# ugs_wifi_pendant_easyeda_source.net
KiCad netlist of a schematic drawn in EasyEDA
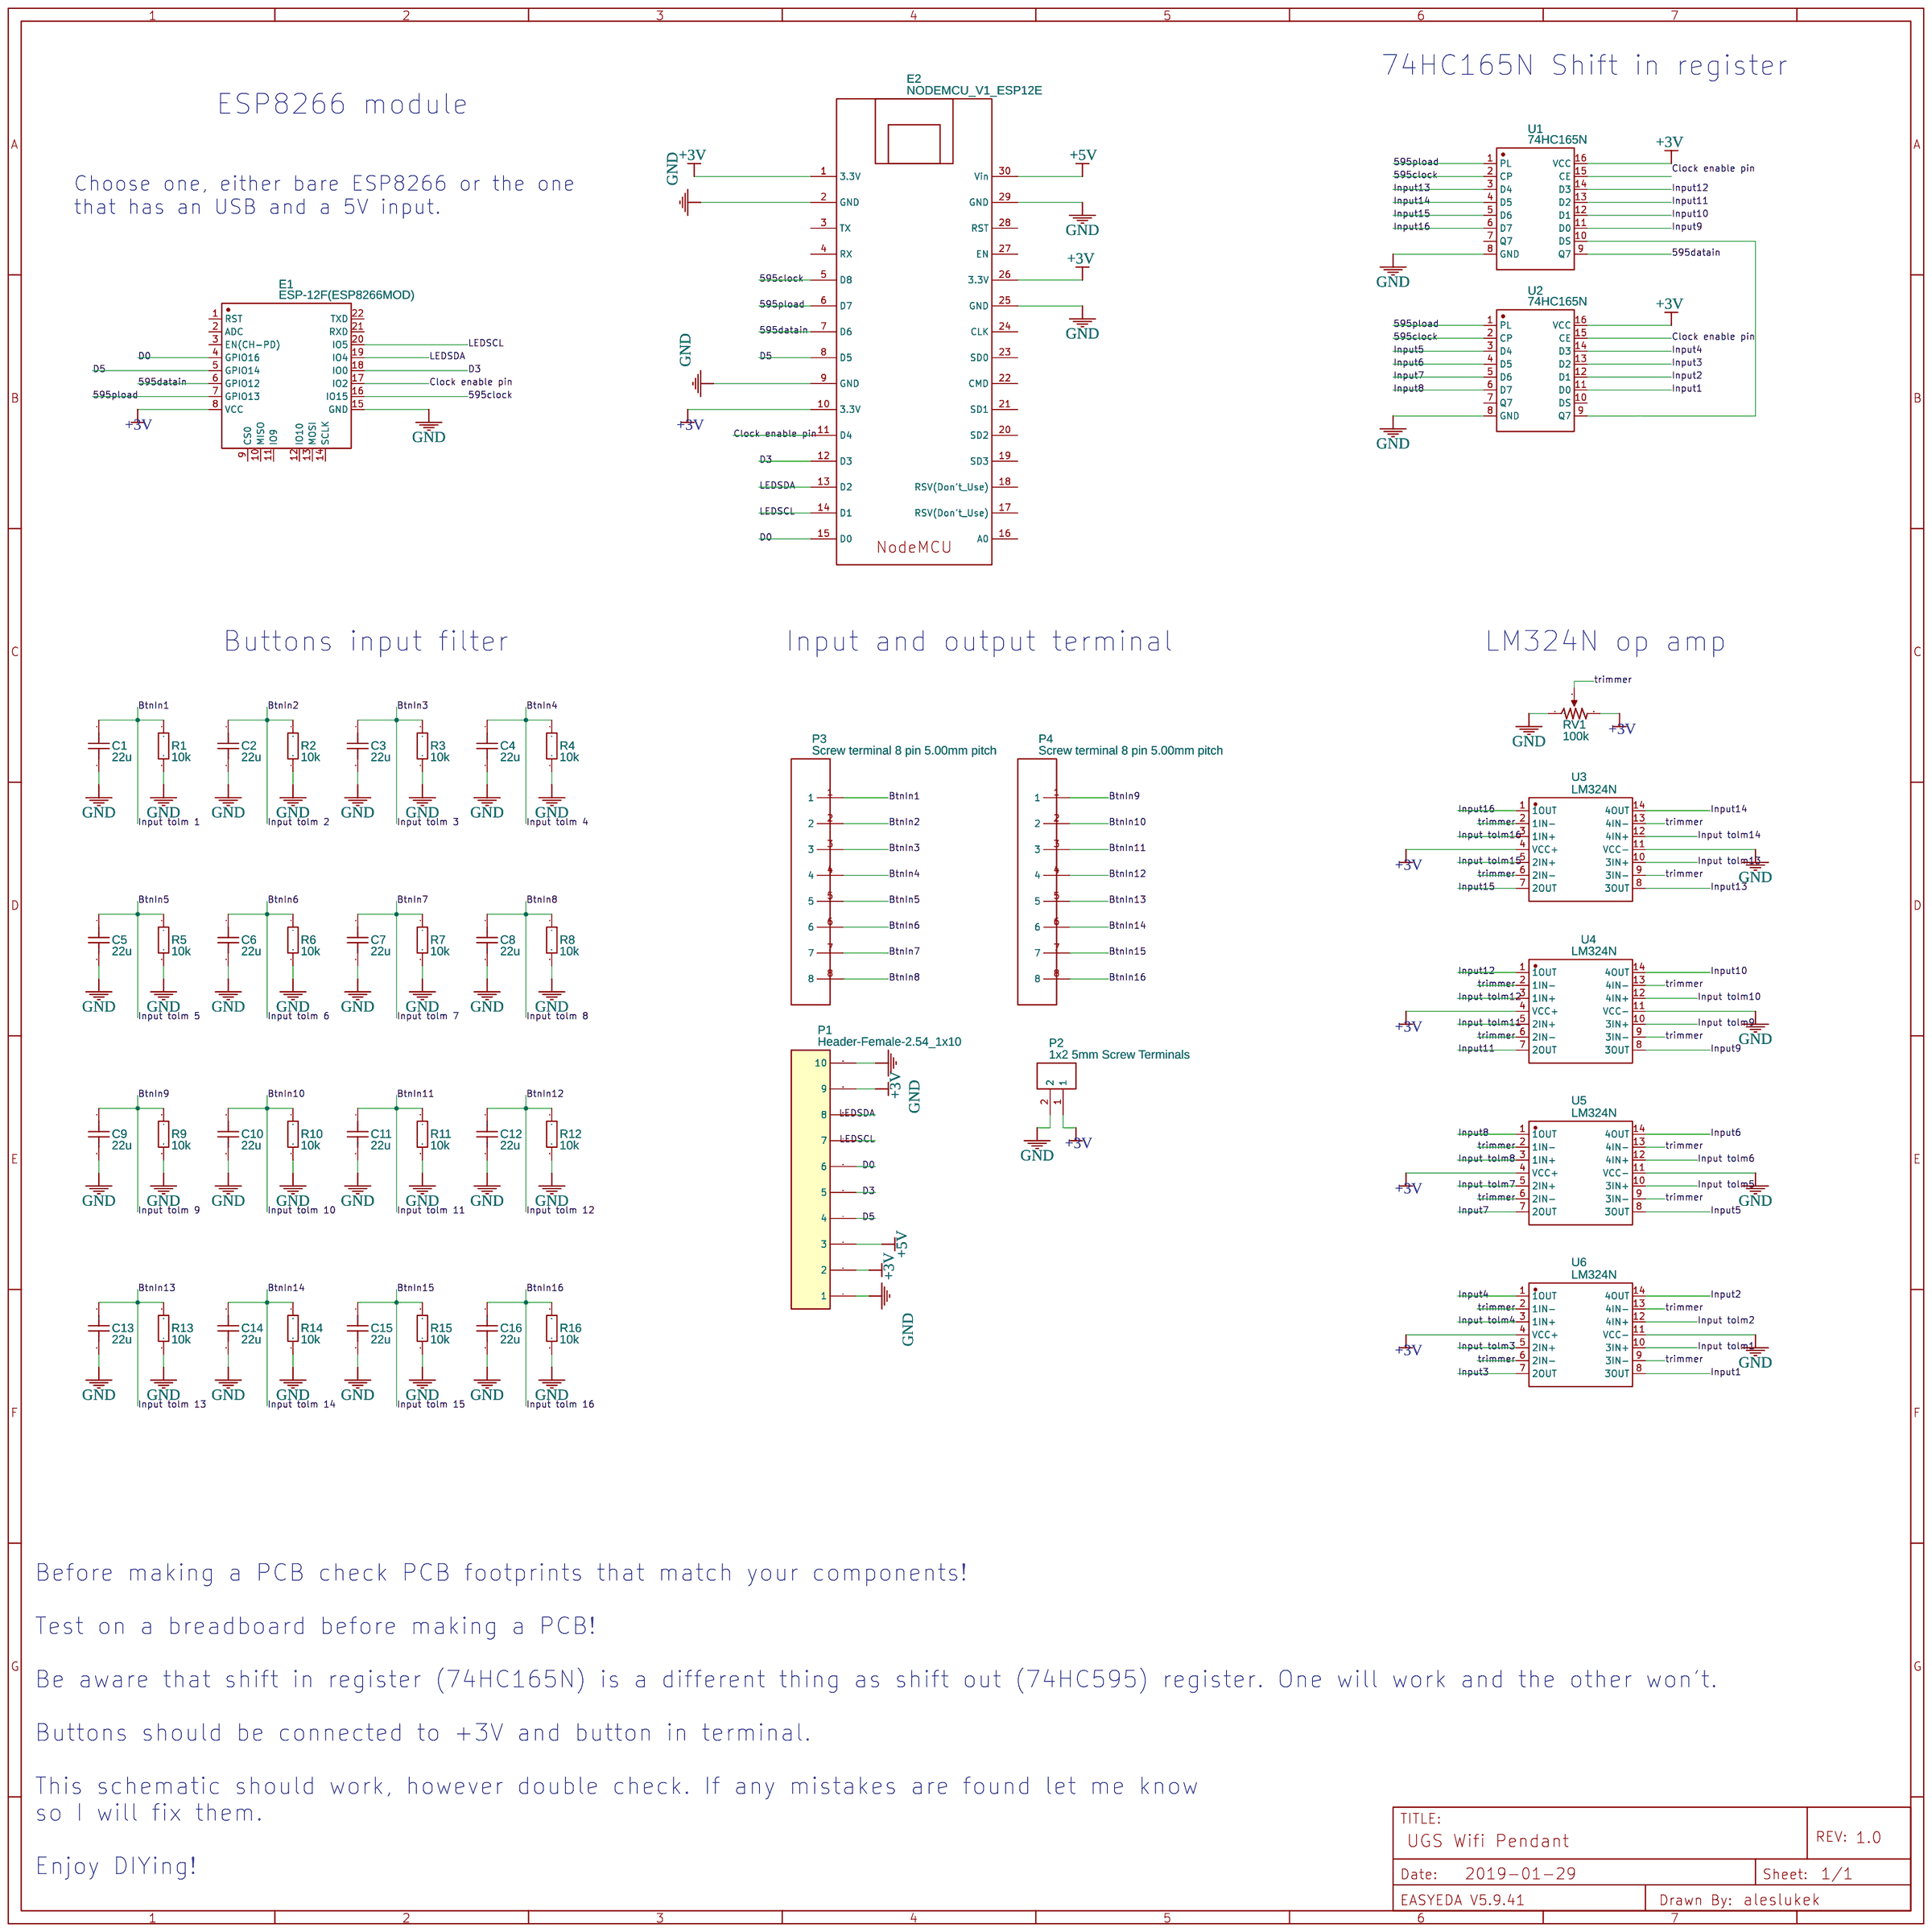
[diagram p0: schematic sheet]

(export (version "E")
  (design (tool "Eeschema 10.0.6"))
  (components
    (comp (ref "C1")
      (value "22u")
      (fields (field (name "BOM_Manufacturer Part") "?"))
      (libsource (lib "") (part "Cap_RAD-0.1_US"))
    )
    (comp (ref "C2")
      (value "22u")
      (fields (field (name "BOM_Manufacturer Part") "?"))
      (libsource (lib "") (part "Cap_RAD-0.1_US"))
    )
    (comp (ref "C3")
      (value "22u")
      (fields (field (name "BOM_Manufacturer Part") "?"))
      (libsource (lib "") (part "Cap_RAD-0.1_US"))
    )
    (comp (ref "C4")
      (value "22u")
      (fields (field (name "BOM_Manufacturer Part") "?"))
      (libsource (lib "") (part "Cap_RAD-0.1_US"))
    )
    (comp (ref "C5")
      (value "22u")
      (fields (field (name "BOM_Manufacturer Part") "?"))
      (libsource (lib "") (part "Cap_RAD-0.1_US"))
    )
    (comp (ref "C6")
      (value "22u")
      (fields (field (name "BOM_Manufacturer Part") "?"))
      (libsource (lib "") (part "Cap_RAD-0.1_US"))
    )
    (comp (ref "C7")
      (value "22u")
      (fields (field (name "BOM_Manufacturer Part") "?"))
      (libsource (lib "") (part "Cap_RAD-0.1_US"))
    )
    (comp (ref "C8")
      (value "22u")
      (fields (field (name "BOM_Manufacturer Part") "?"))
      (libsource (lib "") (part "Cap_RAD-0.1_US"))
    )
    (comp (ref "C9")
      (value "22u")
      (fields (field (name "BOM_Manufacturer Part") "?"))
      (libsource (lib "") (part "Cap_RAD-0.1_US"))
    )
    (comp (ref "C10")
      (value "22u")
      (fields (field (name "BOM_Manufacturer Part") "?"))
      (libsource (lib "") (part "Cap_RAD-0.1_US"))
    )
    (comp (ref "C11")
      (value "22u")
      (fields (field (name "BOM_Manufacturer Part") "?"))
      (libsource (lib "") (part "Cap_RAD-0.1_US"))
    )
    (comp (ref "C12")
      (value "22u")
      (fields (field (name "BOM_Manufacturer Part") "?"))
      (libsource (lib "") (part "Cap_RAD-0.1_US"))
    )
    (comp (ref "C13")
      (value "22u")
      (fields (field (name "BOM_Manufacturer Part") "?"))
      (libsource (lib "") (part "Cap_RAD-0.1_US"))
    )
    (comp (ref "C14")
      (value "22u")
      (fields (field (name "BOM_Manufacturer Part") "?"))
      (libsource (lib "") (part "Cap_RAD-0.1_US"))
    )
    (comp (ref "C15")
      (value "22u")
      (fields (field (name "BOM_Manufacturer Part") "?"))
      (libsource (lib "") (part "Cap_RAD-0.1_US"))
    )
    (comp (ref "C16")
      (value "22u")
      (fields (field (name "BOM_Manufacturer Part") "?"))
      (libsource (lib "") (part "Cap_RAD-0.1_US"))
    )
    (comp (ref "E1")
      (value "ESP-12F(ESP8266MOD)")
      (fields (field (name "BOM_Supplier Part") "C82891"))
      (libsource (lib "") (part "Unknown_215_290"))
    )
    (comp (ref "E2")
      (value "NODEMCU_V1_ESP12E")
      (fields (field (name "BOM_Manufacturer Part") "?"))
      (libsource (lib "") (part "NODEMCU_V1_ESP12E"))
    )
    (comp (ref "P1")
      (value "Header-Female-2.54_1x10")
      (fields (field (name "BOM_Supplier Part") "C35445"))
      (libsource (lib "") (part "Unknown_635_885"))
    )
    (comp (ref "P2") (value "1x2 5mm Screw Terminals") (libsource (lib "") (part "Unknown_805_835")))
    (comp (ref "P3")
      (value "Screw terminal 8 pin 5.00mm pitch")
      (fields (field (name "BOM_Manufacturer Part") "?"))
      (libsource (lib "") (part "Unknown_605_700"))
    )
    (comp (ref "P4")
      (value "Screw terminal 8 pin 5.00mm pitch")
      (fields (field (name "BOM_Manufacturer Part") "?"))
      (libsource (lib "") (part "Unknown_780_700"))
    )
    (comp (ref "R1")
      (value "10k")
      (fields (field (name "BOM_Manufacturer Part") "?"))
      (libsource (lib "") (part "Res_AXIAL-0.3(1/8W)_EU"))
    )
    (comp (ref "R2")
      (value "10k")
      (fields (field (name "BOM_Manufacturer Part") "?"))
      (libsource (lib "") (part "Res_AXIAL-0.3(1/8W)_EU"))
    )
    (comp (ref "R3")
      (value "10k")
      (fields (field (name "BOM_Manufacturer Part") "?"))
      (libsource (lib "") (part "Res_AXIAL-0.3(1/8W)_EU"))
    )
    (comp (ref "R4")
      (value "10k")
      (fields (field (name "BOM_Manufacturer Part") "?"))
      (libsource (lib "") (part "Res_AXIAL-0.3(1/8W)_EU"))
    )
    (comp (ref "R5")
      (value "10k")
      (fields (field (name "BOM_Manufacturer Part") "?"))
      (libsource (lib "") (part "Res_AXIAL-0.3(1/8W)_EU"))
    )
    (comp (ref "R6")
      (value "10k")
      (fields (field (name "BOM_Manufacturer Part") "?"))
      (libsource (lib "") (part "Res_AXIAL-0.3(1/8W)_EU"))
    )
    (comp (ref "R7")
      (value "10k")
      (fields (field (name "BOM_Manufacturer Part") "?"))
      (libsource (lib "") (part "Res_AXIAL-0.3(1/8W)_EU"))
    )
    (comp (ref "R8")
      (value "10k")
      (fields (field (name "BOM_Manufacturer Part") "?"))
      (libsource (lib "") (part "Res_AXIAL-0.3(1/8W)_EU"))
    )
    (comp (ref "R9")
      (value "10k")
      (fields (field (name "BOM_Manufacturer Part") "?"))
      (libsource (lib "") (part "Res_AXIAL-0.3(1/8W)_EU"))
    )
    (comp (ref "R10")
      (value "10k")
      (fields (field (name "BOM_Manufacturer Part") "?"))
      (libsource (lib "") (part "Res_AXIAL-0.3(1/8W)_EU"))
    )
    (comp (ref "R11")
      (value "10k")
      (fields (field (name "BOM_Manufacturer Part") "?"))
      (libsource (lib "") (part "Res_AXIAL-0.3(1/8W)_EU"))
    )
    (comp (ref "R12")
      (value "10k")
      (fields (field (name "BOM_Manufacturer Part") "?"))
      (libsource (lib "") (part "Res_AXIAL-0.3(1/8W)_EU"))
    )
    (comp (ref "R13")
      (value "10k")
      (fields (field (name "BOM_Manufacturer Part") "?"))
      (libsource (lib "") (part "Res_AXIAL-0.3(1/8W)_EU"))
    )
    (comp (ref "R14")
      (value "10k")
      (fields (field (name "BOM_Manufacturer Part") "?"))
      (libsource (lib "") (part "Res_AXIAL-0.3(1/8W)_EU"))
    )
    (comp (ref "R15")
      (value "10k")
      (fields (field (name "BOM_Manufacturer Part") "?"))
      (libsource (lib "") (part "Res_AXIAL-0.3(1/8W)_EU"))
    )
    (comp (ref "R16")
      (value "10k")
      (fields (field (name "BOM_Manufacturer Part") "?"))
      (libsource (lib "") (part "Res_AXIAL-0.3(1/8W)_EU"))
    )
    (comp (ref "RV1")
      (value "100k")
      (fields (field (name "BOM_Manufacturer Part") "?"))
      (libsource (lib "") (part "trimmer"))
    )
    (comp (ref "U1")
      (value "74HC165N")
      (fields (field (name "BOM_Manufacturer Part") "?"))
      (libsource (lib "") (part "Unknown_1180_110"))
    )
    (comp (ref "U2")
      (value "74HC165N")
      (fields (field (name "BOM_Manufacturer Part") "?"))
      (libsource (lib "") (part "Unknown_1180_235"))
    )
    (comp (ref "U3")
      (value "LM324N")
      (fields (field (name "BOM_Supplier Part") "C114380"))
      (libsource (lib "") (part "Unknown_1215_650"))
    )
    (comp (ref "U4")
      (value "LM324N")
      (fields (field (name "BOM_Supplier Part") "C114380"))
      (libsource (lib "") (part "Unknown_1215_775"))
    )
    (comp (ref "U5")
      (value "LM324N")
      (fields (field (name "BOM_Supplier Part") "C114380"))
      (libsource (lib "") (part "Unknown_1215_900"))
    )
    (comp (ref "U6")
      (value "LM324N")
      (fields (field (name "BOM_Supplier Part") "C114380"))
      (libsource (lib "") (part "Unknown_1215_1025"))
    )
  )
  (nets
    (net (code "1") (name "+3V") (class "Default")
      (node (ref "E1") (pin "8") (pinfunction "VCC_8") (pintype "unspecified"))
      (node (ref "E2") (pin "1") (pinfunction "3.3V_1") (pintype "unspecified"))
      (node (ref "E2") (pin "10") (pinfunction "3.3V_10") (pintype "unspecified"))
      (node (ref "E2") (pin "26") (pinfunction "3.3V_26") (pintype "unspecified"))
      (node (ref "P1") (pin "2") (pinfunction "2_2") (pintype "input"))
      (node (ref "P1") (pin "9") (pinfunction "9_9") (pintype "input"))
      (node (ref "P2") (pin "1") (pinfunction "1_1") (pintype "unspecified"))
      (node (ref "RV1") (pin "3") (pinfunction "3_3") (pintype "unspecified"))
      (node (ref "U1") (pin "16") (pinfunction "VCC_16") (pintype "unspecified"))
      (node (ref "U2") (pin "16") (pinfunction "VCC_16") (pintype "unspecified"))
      (node (ref "U3") (pin "4") (pinfunction "VCC+_4") (pintype "unspecified"))
      (node (ref "U4") (pin "4") (pinfunction "VCC+_4") (pintype "unspecified"))
      (node (ref "U5") (pin "4") (pinfunction "VCC+_4") (pintype "unspecified"))
      (node (ref "U6") (pin "4") (pinfunction "VCC+_4") (pintype "unspecified"))
    )
    (net (code "2") (name "+5V") (class "Default")
      (node (ref "E2") (pin "30") (pinfunction "Vin_30") (pintype "unspecified"))
      (node (ref "P1") (pin "3") (pinfunction "3_3") (pintype "input"))
    )
    (net (code "3") (name "/595clock") (class "Default")
      (node (ref "E1") (pin "16") (pinfunction "IO15_16") (pintype "unspecified"))
      (node (ref "E2") (pin "5") (pinfunction "D8_5") (pintype "unspecified"))
      (node (ref "U1") (pin "2") (pinfunction "CP_2") (pintype "unspecified"))
      (node (ref "U2") (pin "2") (pinfunction "CP_2") (pintype "unspecified"))
    )
    (net (code "4") (name "/595datain") (class "Default")
      (node (ref "E1") (pin "6") (pinfunction "GPIO12_6") (pintype "unspecified"))
      (node (ref "E2") (pin "7") (pinfunction "D6_7") (pintype "unspecified"))
      (node (ref "U1") (pin "9") (pinfunction "Q7_9") (pintype "unspecified"))
    )
    (net (code "5") (name "/595pload") (class "Default")
      (node (ref "E1") (pin "7") (pinfunction "GPIO13_7") (pintype "unspecified"))
      (node (ref "E2") (pin "6") (pinfunction "D7_6") (pintype "unspecified"))
      (node (ref "U1") (pin "1") (pinfunction "PL_1") (pintype "unspecified"))
      (node (ref "U2") (pin "1") (pinfunction "PL_1") (pintype "unspecified"))
    )
    (net (code "6") (name "/BtnIn1") (class "Default")
      (node (ref "C1") (pin "1") (pinfunction "1_1") (pintype "unspecified"))
      (node (ref "P3") (pin "1") (pinfunction "1_1") (pintype "unspecified"))
      (node (ref "R1") (pin "1") (pinfunction "1_1") (pintype "unspecified"))
    )
    (net (code "7") (name "/BtnIn2") (class "Default")
      (node (ref "C2") (pin "1") (pinfunction "1_1") (pintype "unspecified"))
      (node (ref "P3") (pin "2") (pinfunction "2_2") (pintype "unspecified"))
      (node (ref "R2") (pin "1") (pinfunction "1_1") (pintype "unspecified"))
    )
    (net (code "8") (name "/BtnIn3") (class "Default")
      (node (ref "C3") (pin "1") (pinfunction "1_1") (pintype "unspecified"))
      (node (ref "P3") (pin "3") (pinfunction "3_3") (pintype "unspecified"))
      (node (ref "R3") (pin "1") (pinfunction "1_1") (pintype "unspecified"))
    )
    (net (code "9") (name "/BtnIn4") (class "Default")
      (node (ref "C4") (pin "1") (pinfunction "1_1") (pintype "unspecified"))
      (node (ref "P3") (pin "4") (pinfunction "4_4") (pintype "unspecified"))
      (node (ref "R4") (pin "1") (pinfunction "1_1") (pintype "unspecified"))
    )
    (net (code "10") (name "/BtnIn5") (class "Default")
      (node (ref "C5") (pin "1") (pinfunction "1_1") (pintype "unspecified"))
      (node (ref "P3") (pin "5") (pinfunction "5_5") (pintype "unspecified"))
      (node (ref "R5") (pin "1") (pinfunction "1_1") (pintype "unspecified"))
    )
    (net (code "11") (name "/BtnIn6") (class "Default")
      (node (ref "C6") (pin "1") (pinfunction "1_1") (pintype "unspecified"))
      (node (ref "P3") (pin "6") (pinfunction "6_6") (pintype "unspecified"))
      (node (ref "R6") (pin "1") (pinfunction "1_1") (pintype "unspecified"))
    )
    (net (code "12") (name "/BtnIn7") (class "Default")
      (node (ref "C7") (pin "1") (pinfunction "1_1") (pintype "unspecified"))
      (node (ref "P3") (pin "7") (pinfunction "7_7") (pintype "unspecified"))
      (node (ref "R7") (pin "1") (pinfunction "1_1") (pintype "unspecified"))
    )
    (net (code "13") (name "/BtnIn8") (class "Default")
      (node (ref "C8") (pin "1") (pinfunction "1_1") (pintype "unspecified"))
      (node (ref "P3") (pin "8") (pinfunction "8_8") (pintype "unspecified"))
      (node (ref "R8") (pin "1") (pinfunction "1_1") (pintype "unspecified"))
    )
    (net (code "14") (name "/BtnIn9") (class "Default")
      (node (ref "C9") (pin "1") (pinfunction "1_1") (pintype "unspecified"))
      (node (ref "P4") (pin "1") (pinfunction "1_1") (pintype "unspecified"))
      (node (ref "R9") (pin "1") (pinfunction "1_1") (pintype "unspecified"))
    )
    (net (code "15") (name "/BtnIn10") (class "Default")
      (node (ref "C10") (pin "1") (pinfunction "1_1") (pintype "unspecified"))
      (node (ref "P4") (pin "2") (pinfunction "2_2") (pintype "unspecified"))
      (node (ref "R10") (pin "1") (pinfunction "1_1") (pintype "unspecified"))
    )
    (net (code "16") (name "/BtnIn11") (class "Default")
      (node (ref "C11") (pin "1") (pinfunction "1_1") (pintype "unspecified"))
      (node (ref "P4") (pin "3") (pinfunction "3_3") (pintype "unspecified"))
      (node (ref "R11") (pin "1") (pinfunction "1_1") (pintype "unspecified"))
    )
    (net (code "17") (name "/BtnIn12") (class "Default")
      (node (ref "C12") (pin "1") (pinfunction "1_1") (pintype "unspecified"))
      (node (ref "P4") (pin "4") (pinfunction "4_4") (pintype "unspecified"))
      (node (ref "R12") (pin "1") (pinfunction "1_1") (pintype "unspecified"))
    )
    (net (code "18") (name "/BtnIn13") (class "Default")
      (node (ref "C13") (pin "1") (pinfunction "1_1") (pintype "unspecified"))
      (node (ref "P4") (pin "5") (pinfunction "5_5") (pintype "unspecified"))
      (node (ref "R13") (pin "1") (pinfunction "1_1") (pintype "unspecified"))
    )
    (net (code "19") (name "/BtnIn14") (class "Default")
      (node (ref "C14") (pin "1") (pinfunction "1_1") (pintype "unspecified"))
      (node (ref "P4") (pin "6") (pinfunction "6_6") (pintype "unspecified"))
      (node (ref "R14") (pin "1") (pinfunction "1_1") (pintype "unspecified"))
    )
    (net (code "20") (name "/BtnIn15") (class "Default")
      (node (ref "C15") (pin "1") (pinfunction "1_1") (pintype "unspecified"))
      (node (ref "P4") (pin "7") (pinfunction "7_7") (pintype "unspecified"))
      (node (ref "R15") (pin "1") (pinfunction "1_1") (pintype "unspecified"))
    )
    (net (code "21") (name "/BtnIn16") (class "Default")
      (node (ref "C16") (pin "1") (pinfunction "1_1") (pintype "unspecified"))
      (node (ref "P4") (pin "8") (pinfunction "8_8") (pintype "unspecified"))
      (node (ref "R16") (pin "1") (pinfunction "1_1") (pintype "unspecified"))
    )
    (net (code "22") (name "/Clock enable pin") (class "Default")
      (node (ref "E1") (pin "17") (pinfunction "IO2_17") (pintype "unspecified"))
      (node (ref "E2") (pin "11") (pinfunction "D4_11") (pintype "unspecified"))
      (node (ref "U2") (pin "15") (pinfunction "CE_15") (pintype "unspecified"))
    )
    (net (code "23") (name "/D0") (class "Default")
      (node (ref "E1") (pin "4") (pinfunction "GPIO16_4") (pintype "unspecified"))
      (node (ref "E2") (pin "15") (pinfunction "D0_15") (pintype "unspecified"))
      (node (ref "P1") (pin "6") (pinfunction "6_6") (pintype "input"))
    )
    (net (code "24") (name "/D3") (class "Default")
      (node (ref "E1") (pin "18") (pinfunction "IO0_18") (pintype "unspecified"))
      (node (ref "E2") (pin "12") (pinfunction "D3_12") (pintype "unspecified"))
      (node (ref "P1") (pin "5") (pinfunction "5_5") (pintype "input"))
    )
    (net (code "25") (name "/D5") (class "Default")
      (node (ref "E1") (pin "5") (pinfunction "GPIO14_5") (pintype "unspecified"))
      (node (ref "E2") (pin "8") (pinfunction "D5_8") (pintype "unspecified"))
      (node (ref "P1") (pin "4") (pinfunction "4_4") (pintype "input"))
    )
    (net (code "26") (name "/Input tolm1") (class "Default")
      (node (ref "U6") (pin "10") (pinfunction "3IN+_10") (pintype "unspecified"))
    )
    (net (code "27") (name "/Input tolm2") (class "Default")
      (node (ref "U6") (pin "12") (pinfunction "4IN+_12") (pintype "unspecified"))
    )
    (net (code "28") (name "/Input tolm3") (class "Default")
      (node (ref "U6") (pin "5") (pinfunction "2IN+_5") (pintype "unspecified"))
    )
    (net (code "29") (name "/Input tolm4") (class "Default")
      (node (ref "U6") (pin "3") (pinfunction "1IN+_3") (pintype "unspecified"))
    )
    (net (code "30") (name "/Input tolm5") (class "Default")
      (node (ref "U5") (pin "10") (pinfunction "3IN+_10") (pintype "unspecified"))
    )
    (net (code "31") (name "/Input tolm6") (class "Default")
      (node (ref "U5") (pin "12") (pinfunction "4IN+_12") (pintype "unspecified"))
    )
    (net (code "32") (name "/Input tolm7") (class "Default")
      (node (ref "U5") (pin "5") (pinfunction "2IN+_5") (pintype "unspecified"))
    )
    (net (code "33") (name "/Input tolm8") (class "Default")
      (node (ref "U5") (pin "3") (pinfunction "1IN+_3") (pintype "unspecified"))
    )
    (net (code "34") (name "/Input tolm9") (class "Default")
      (node (ref "U4") (pin "10") (pinfunction "3IN+_10") (pintype "unspecified"))
    )
    (net (code "35") (name "/Input tolm10") (class "Default")
      (node (ref "U4") (pin "12") (pinfunction "4IN+_12") (pintype "unspecified"))
    )
    (net (code "36") (name "/Input tolm11") (class "Default")
      (node (ref "U4") (pin "5") (pinfunction "2IN+_5") (pintype "unspecified"))
    )
    (net (code "37") (name "/Input tolm12") (class "Default")
      (node (ref "U4") (pin "3") (pinfunction "1IN+_3") (pintype "unspecified"))
    )
    (net (code "38") (name "/Input tolm13") (class "Default")
      (node (ref "U3") (pin "10") (pinfunction "3IN+_10") (pintype "unspecified"))
    )
    (net (code "39") (name "/Input tolm14") (class "Default")
      (node (ref "U3") (pin "12") (pinfunction "4IN+_12") (pintype "unspecified"))
    )
    (net (code "40") (name "/Input tolm15") (class "Default")
      (node (ref "U3") (pin "5") (pinfunction "2IN+_5") (pintype "unspecified"))
    )
    (net (code "41") (name "/Input tolm16") (class "Default")
      (node (ref "U3") (pin "3") (pinfunction "1IN+_3") (pintype "unspecified"))
    )
    (net (code "42") (name "/Input1") (class "Default")
      (node (ref "U2") (pin "11") (pinfunction "D0_11") (pintype "unspecified"))
      (node (ref "U6") (pin "8") (pinfunction "3OUT_8") (pintype "unspecified"))
    )
    (net (code "43") (name "/Input2") (class "Default")
      (node (ref "U2") (pin "12") (pinfunction "D1_12") (pintype "unspecified"))
      (node (ref "U6") (pin "14") (pinfunction "4OUT_14") (pintype "unspecified"))
    )
    (net (code "44") (name "/Input3") (class "Default")
      (node (ref "U2") (pin "13") (pinfunction "D2_13") (pintype "unspecified"))
      (node (ref "U6") (pin "7") (pinfunction "2OUT_7") (pintype "unspecified"))
    )
    (net (code "45") (name "/Input4") (class "Default")
      (node (ref "U2") (pin "14") (pinfunction "D3_14") (pintype "unspecified"))
      (node (ref "U6") (pin "1") (pinfunction "1OUT_1") (pintype "unspecified"))
    )
    (net (code "46") (name "/Input5") (class "Default")
      (node (ref "U2") (pin "3") (pinfunction "D4_3") (pintype "unspecified"))
      (node (ref "U5") (pin "8") (pinfunction "3OUT_8") (pintype "unspecified"))
    )
    (net (code "47") (name "/Input6") (class "Default")
      (node (ref "U2") (pin "4") (pinfunction "D5_4") (pintype "unspecified"))
      (node (ref "U5") (pin "14") (pinfunction "4OUT_14") (pintype "unspecified"))
    )
    (net (code "48") (name "/Input7") (class "Default")
      (node (ref "U2") (pin "5") (pinfunction "D6_5") (pintype "unspecified"))
      (node (ref "U5") (pin "7") (pinfunction "2OUT_7") (pintype "unspecified"))
    )
    (net (code "49") (name "/Input8") (class "Default")
      (node (ref "U2") (pin "6") (pinfunction "D7_6") (pintype "unspecified"))
      (node (ref "U5") (pin "1") (pinfunction "1OUT_1") (pintype "unspecified"))
    )
    (net (code "50") (name "/Input9") (class "Default")
      (node (ref "U1") (pin "11") (pinfunction "D0_11") (pintype "unspecified"))
      (node (ref "U4") (pin "8") (pinfunction "3OUT_8") (pintype "unspecified"))
    )
    (net (code "51") (name "/Input10") (class "Default")
      (node (ref "U1") (pin "12") (pinfunction "D1_12") (pintype "unspecified"))
      (node (ref "U4") (pin "14") (pinfunction "4OUT_14") (pintype "unspecified"))
    )
    (net (code "52") (name "/Input11") (class "Default")
      (node (ref "U1") (pin "13") (pinfunction "D2_13") (pintype "unspecified"))
      (node (ref "U4") (pin "7") (pinfunction "2OUT_7") (pintype "unspecified"))
    )
    (net (code "53") (name "/Input12") (class "Default")
      (node (ref "U1") (pin "14") (pinfunction "D3_14") (pintype "unspecified"))
      (node (ref "U4") (pin "1") (pinfunction "1OUT_1") (pintype "unspecified"))
    )
    (net (code "54") (name "/Input13") (class "Default")
      (node (ref "U1") (pin "3") (pinfunction "D4_3") (pintype "unspecified"))
      (node (ref "U3") (pin "8") (pinfunction "3OUT_8") (pintype "unspecified"))
    )
    (net (code "55") (name "/Input14") (class "Default")
      (node (ref "U1") (pin "4") (pinfunction "D5_4") (pintype "unspecified"))
      (node (ref "U3") (pin "14") (pinfunction "4OUT_14") (pintype "unspecified"))
    )
    (net (code "56") (name "/Input15") (class "Default")
      (node (ref "U1") (pin "5") (pinfunction "D6_5") (pintype "unspecified"))
      (node (ref "U3") (pin "7") (pinfunction "2OUT_7") (pintype "unspecified"))
    )
    (net (code "57") (name "/Input16") (class "Default")
      (node (ref "U1") (pin "6") (pinfunction "D7_6") (pintype "unspecified"))
      (node (ref "U3") (pin "1") (pinfunction "1OUT_1") (pintype "unspecified"))
    )
    (net (code "58") (name "/LEDSCL") (class "Default")
      (node (ref "E1") (pin "20") (pinfunction "IO5_20") (pintype "unspecified"))
      (node (ref "E2") (pin "14") (pinfunction "D1_14") (pintype "unspecified"))
      (node (ref "P1") (pin "7") (pinfunction "7_7") (pintype "input"))
    )
    (net (code "59") (name "/LEDSDA") (class "Default")
      (node (ref "E1") (pin "19") (pinfunction "IO4_19") (pintype "unspecified"))
      (node (ref "E2") (pin "13") (pinfunction "D2_13") (pintype "unspecified"))
      (node (ref "P1") (pin "8") (pinfunction "8_8") (pintype "input"))
    )
    (net (code "60") (name "/trimmer") (class "Default")
      (node (ref "RV1") (pin "2") (pinfunction "2_2") (pintype "unspecified"))
      (node (ref "U3") (pin "13") (pinfunction "4IN-_13") (pintype "unspecified"))
      (node (ref "U3") (pin "2") (pinfunction "1IN-_2") (pintype "unspecified"))
      (node (ref "U3") (pin "6") (pinfunction "2IN-_6") (pintype "unspecified"))
      (node (ref "U3") (pin "9") (pinfunction "3IN-_9") (pintype "unspecified"))
      (node (ref "U4") (pin "13") (pinfunction "4IN-_13") (pintype "unspecified"))
      (node (ref "U4") (pin "2") (pinfunction "1IN-_2") (pintype "unspecified"))
      (node (ref "U4") (pin "6") (pinfunction "2IN-_6") (pintype "unspecified"))
      (node (ref "U4") (pin "9") (pinfunction "3IN-_9") (pintype "unspecified"))
      (node (ref "U5") (pin "13") (pinfunction "4IN-_13") (pintype "unspecified"))
      (node (ref "U5") (pin "2") (pinfunction "1IN-_2") (pintype "unspecified"))
      (node (ref "U5") (pin "6") (pinfunction "2IN-_6") (pintype "unspecified"))
      (node (ref "U5") (pin "9") (pinfunction "3IN-_9") (pintype "unspecified"))
      (node (ref "U6") (pin "13") (pinfunction "4IN-_13") (pintype "unspecified"))
      (node (ref "U6") (pin "2") (pinfunction "1IN-_2") (pintype "unspecified"))
      (node (ref "U6") (pin "6") (pinfunction "2IN-_6") (pintype "unspecified"))
      (node (ref "U6") (pin "9") (pinfunction "3IN-_9") (pintype "unspecified"))
    )
    (net (code "61") (name "GND") (class "Default")
      (node (ref "C1") (pin "2") (pinfunction "2_2") (pintype "unspecified"))
      (node (ref "C10") (pin "2") (pinfunction "2_2") (pintype "unspecified"))
      (node (ref "C11") (pin "2") (pinfunction "2_2") (pintype "unspecified"))
      (node (ref "C12") (pin "2") (pinfunction "2_2") (pintype "unspecified"))
      (node (ref "C13") (pin "2") (pinfunction "2_2") (pintype "unspecified"))
      (node (ref "C14") (pin "2") (pinfunction "2_2") (pintype "unspecified"))
      (node (ref "C15") (pin "2") (pinfunction "2_2") (pintype "unspecified"))
      (node (ref "C16") (pin "2") (pinfunction "2_2") (pintype "unspecified"))
      (node (ref "C2") (pin "2") (pinfunction "2_2") (pintype "unspecified"))
      (node (ref "C3") (pin "2") (pinfunction "2_2") (pintype "unspecified"))
      (node (ref "C4") (pin "2") (pinfunction "2_2") (pintype "unspecified"))
      (node (ref "C5") (pin "2") (pinfunction "2_2") (pintype "unspecified"))
      (node (ref "C6") (pin "2") (pinfunction "2_2") (pintype "unspecified"))
      (node (ref "C7") (pin "2") (pinfunction "2_2") (pintype "unspecified"))
      (node (ref "C8") (pin "2") (pinfunction "2_2") (pintype "unspecified"))
      (node (ref "C9") (pin "2") (pinfunction "2_2") (pintype "unspecified"))
      (node (ref "E1") (pin "15") (pinfunction "GND_15") (pintype "unspecified"))
      (node (ref "E2") (pin "2") (pinfunction "GND_2") (pintype "unspecified"))
      (node (ref "E2") (pin "25") (pinfunction "GND_25") (pintype "unspecified"))
      (node (ref "E2") (pin "29") (pinfunction "GND_29") (pintype "unspecified"))
      (node (ref "E2") (pin "9") (pinfunction "GND_9") (pintype "unspecified"))
      (node (ref "P1") (pin "1") (pinfunction "1_1") (pintype "input"))
      (node (ref "P1") (pin "10") (pinfunction "10_10") (pintype "input"))
      (node (ref "P2") (pin "2") (pinfunction "2_2") (pintype "unspecified"))
      (node (ref "R1") (pin "2") (pinfunction "2_2") (pintype "unspecified"))
      (node (ref "R10") (pin "2") (pinfunction "2_2") (pintype "unspecified"))
      (node (ref "R11") (pin "2") (pinfunction "2_2") (pintype "unspecified"))
      (node (ref "R12") (pin "2") (pinfunction "2_2") (pintype "unspecified"))
      (node (ref "R13") (pin "2") (pinfunction "2_2") (pintype "unspecified"))
      (node (ref "R14") (pin "2") (pinfunction "2_2") (pintype "unspecified"))
      (node (ref "R15") (pin "2") (pinfunction "2_2") (pintype "unspecified"))
      (node (ref "R16") (pin "2") (pinfunction "2_2") (pintype "unspecified"))
      (node (ref "R2") (pin "2") (pinfunction "2_2") (pintype "unspecified"))
      (node (ref "R3") (pin "2") (pinfunction "2_2") (pintype "unspecified"))
      (node (ref "R4") (pin "2") (pinfunction "2_2") (pintype "unspecified"))
      (node (ref "R5") (pin "2") (pinfunction "2_2") (pintype "unspecified"))
      (node (ref "R6") (pin "2") (pinfunction "2_2") (pintype "unspecified"))
      (node (ref "R7") (pin "2") (pinfunction "2_2") (pintype "unspecified"))
      (node (ref "R8") (pin "2") (pinfunction "2_2") (pintype "unspecified"))
      (node (ref "R9") (pin "2") (pinfunction "2_2") (pintype "unspecified"))
      (node (ref "RV1") (pin "1") (pinfunction "1_1") (pintype "unspecified"))
      (node (ref "U1") (pin "8") (pinfunction "GND_8") (pintype "unspecified"))
      (node (ref "U2") (pin "8") (pinfunction "GND_8") (pintype "unspecified"))
      (node (ref "U3") (pin "11") (pinfunction "VCC-_11") (pintype "unspecified"))
      (node (ref "U4") (pin "11") (pinfunction "VCC-_11") (pintype "unspecified"))
      (node (ref "U5") (pin "11") (pinfunction "VCC-_11") (pintype "unspecified"))
      (node (ref "U6") (pin "11") (pinfunction "VCC-_11") (pintype "unspecified"))
    )
    (net (code "62") (name "Net-(U1-DS)") (class "Default")
      (node (ref "U1") (pin "10") (pinfunction "DS_10") (pintype "unspecified"))
      (node (ref "U2") (pin "9") (pinfunction "Q7_9") (pintype "unspecified"))
    )
    (net (code "63") (name "unconnected-(E1-ADC-Pad2)") (class "Default")
      (node (ref "E1") (pin "2") (pinfunction "ADC_2") (pintype "unspecified"))
    )
    (net (code "64") (name "unconnected-(E1-CS0-Pad9)") (class "Default")
      (node (ref "E1") (pin "9") (pinfunction "CS0_9") (pintype "unspecified"))
    )
    (net (code "65") (name "unconnected-(E1-EN(CH-PD)-Pad3)") (class "Default")
      (node (ref "E1") (pin "3") (pinfunction "EN(CH-PD)_3") (pintype "unspecified"))
    )
    (net (code "66") (name "unconnected-(E1-IO9-Pad11)") (class "Default")
      (node (ref "E1") (pin "11") (pinfunction "IO9_11") (pintype "unspecified"))
    )
    (net (code "67") (name "unconnected-(E1-IO10-Pad12)") (class "Default")
      (node (ref "E1") (pin "12") (pinfunction "IO10_12") (pintype "unspecified"))
    )
    (net (code "68") (name "unconnected-(E1-MISO-Pad10)") (class "Default")
      (node (ref "E1") (pin "10") (pinfunction "MISO_10") (pintype "unspecified"))
    )
    (net (code "69") (name "unconnected-(E1-MOSI-Pad13)") (class "Default")
      (node (ref "E1") (pin "13") (pinfunction "MOSI_13") (pintype "unspecified"))
    )
    (net (code "70") (name "unconnected-(E1-RST-Pad1)") (class "Default")
      (node (ref "E1") (pin "1") (pinfunction "RST_1") (pintype "unspecified"))
    )
    (net (code "71") (name "unconnected-(E1-RXD-Pad21)") (class "Default")
      (node (ref "E1") (pin "21") (pinfunction "RXD_21") (pintype "unspecified"))
    )
    (net (code "72") (name "unconnected-(E1-SCLK-Pad14)") (class "Default")
      (node (ref "E1") (pin "14") (pinfunction "SCLK_14") (pintype "unspecified"))
    )
    (net (code "73") (name "unconnected-(E1-TXD-Pad22)") (class "Default")
      (node (ref "E1") (pin "22") (pinfunction "TXD_22") (pintype "unspecified"))
    )
    (net (code "74") (name "unconnected-(E2-A0-Pad16)") (class "Default")
      (node (ref "E2") (pin "16") (pinfunction "A0_16") (pintype "unspecified"))
    )
    (net (code "75") (name "unconnected-(E2-CLK-Pad24)") (class "Default")
      (node (ref "E2") (pin "24") (pinfunction "CLK_24") (pintype "unspecified"))
    )
    (net (code "76") (name "unconnected-(E2-CMD-Pad22)") (class "Default")
      (node (ref "E2") (pin "22") (pinfunction "CMD_22") (pintype "unspecified"))
    )
    (net (code "77") (name "unconnected-(E2-EN-Pad27)") (class "Default")
      (node (ref "E2") (pin "27") (pinfunction "EN_27") (pintype "unspecified"))
    )
    (net (code "78") (name "unconnected-(E2-RST-Pad28)") (class "Default")
      (node (ref "E2") (pin "28") (pinfunction "RST_28") (pintype "unspecified"))
    )
    (net (code "79") (name "unconnected-(E2-RSV(Don't_Use)-Pad17)") (class "Default")
      (node (ref "E2") (pin "17") (pinfunction "RSV(Don't_Use)_17") (pintype "unspecified"))
    )
    (net (code "80") (name "unconnected-(E2-RSV(Don't_Use)-Pad18)") (class "Default")
      (node (ref "E2") (pin "18") (pinfunction "RSV(Don't_Use)_18") (pintype "unspecified"))
    )
    (net (code "81") (name "unconnected-(E2-RX-Pad4)") (class "Default")
      (node (ref "E2") (pin "4") (pinfunction "RX_4") (pintype "unspecified"))
    )
    (net (code "82") (name "unconnected-(E2-SD0-Pad23)") (class "Default")
      (node (ref "E2") (pin "23") (pinfunction "SD0_23") (pintype "unspecified"))
    )
    (net (code "83") (name "unconnected-(E2-SD1-Pad21)") (class "Default")
      (node (ref "E2") (pin "21") (pinfunction "SD1_21") (pintype "unspecified"))
    )
    (net (code "84") (name "unconnected-(E2-SD2-Pad20)") (class "Default")
      (node (ref "E2") (pin "20") (pinfunction "SD2_20") (pintype "unspecified"))
    )
    (net (code "85") (name "unconnected-(E2-SD3-Pad19)") (class "Default")
      (node (ref "E2") (pin "19") (pinfunction "SD3_19") (pintype "unspecified"))
    )
    (net (code "86") (name "unconnected-(E2-TX-Pad3)") (class "Default")
      (node (ref "E2") (pin "3") (pinfunction "TX_3") (pintype "unspecified"))
    )
    (net (code "87") (name "unconnected-(U1-CE-Pad15)") (class "Default")
      (node (ref "U1") (pin "15") (pinfunction "CE_15") (pintype "unspecified"))
    )
    (net (code "88") (name "unconnected-(U1-Q7-Pad7)") (class "Default")
      (node (ref "U1") (pin "7") (pinfunction "Q7_7") (pintype "unspecified"))
    )
    (net (code "89") (name "unconnected-(U2-DS-Pad10)") (class "Default")
      (node (ref "U2") (pin "10") (pinfunction "DS_10") (pintype "unspecified"))
    )
    (net (code "90") (name "unconnected-(U2-Q7-Pad7)") (class "Default")
      (node (ref "U2") (pin "7") (pinfunction "Q7_7") (pintype "unspecified"))
    )
  )
)
